# PCBPayloadV8.net
KiCad netlist of a schematic drawn in EAGLE
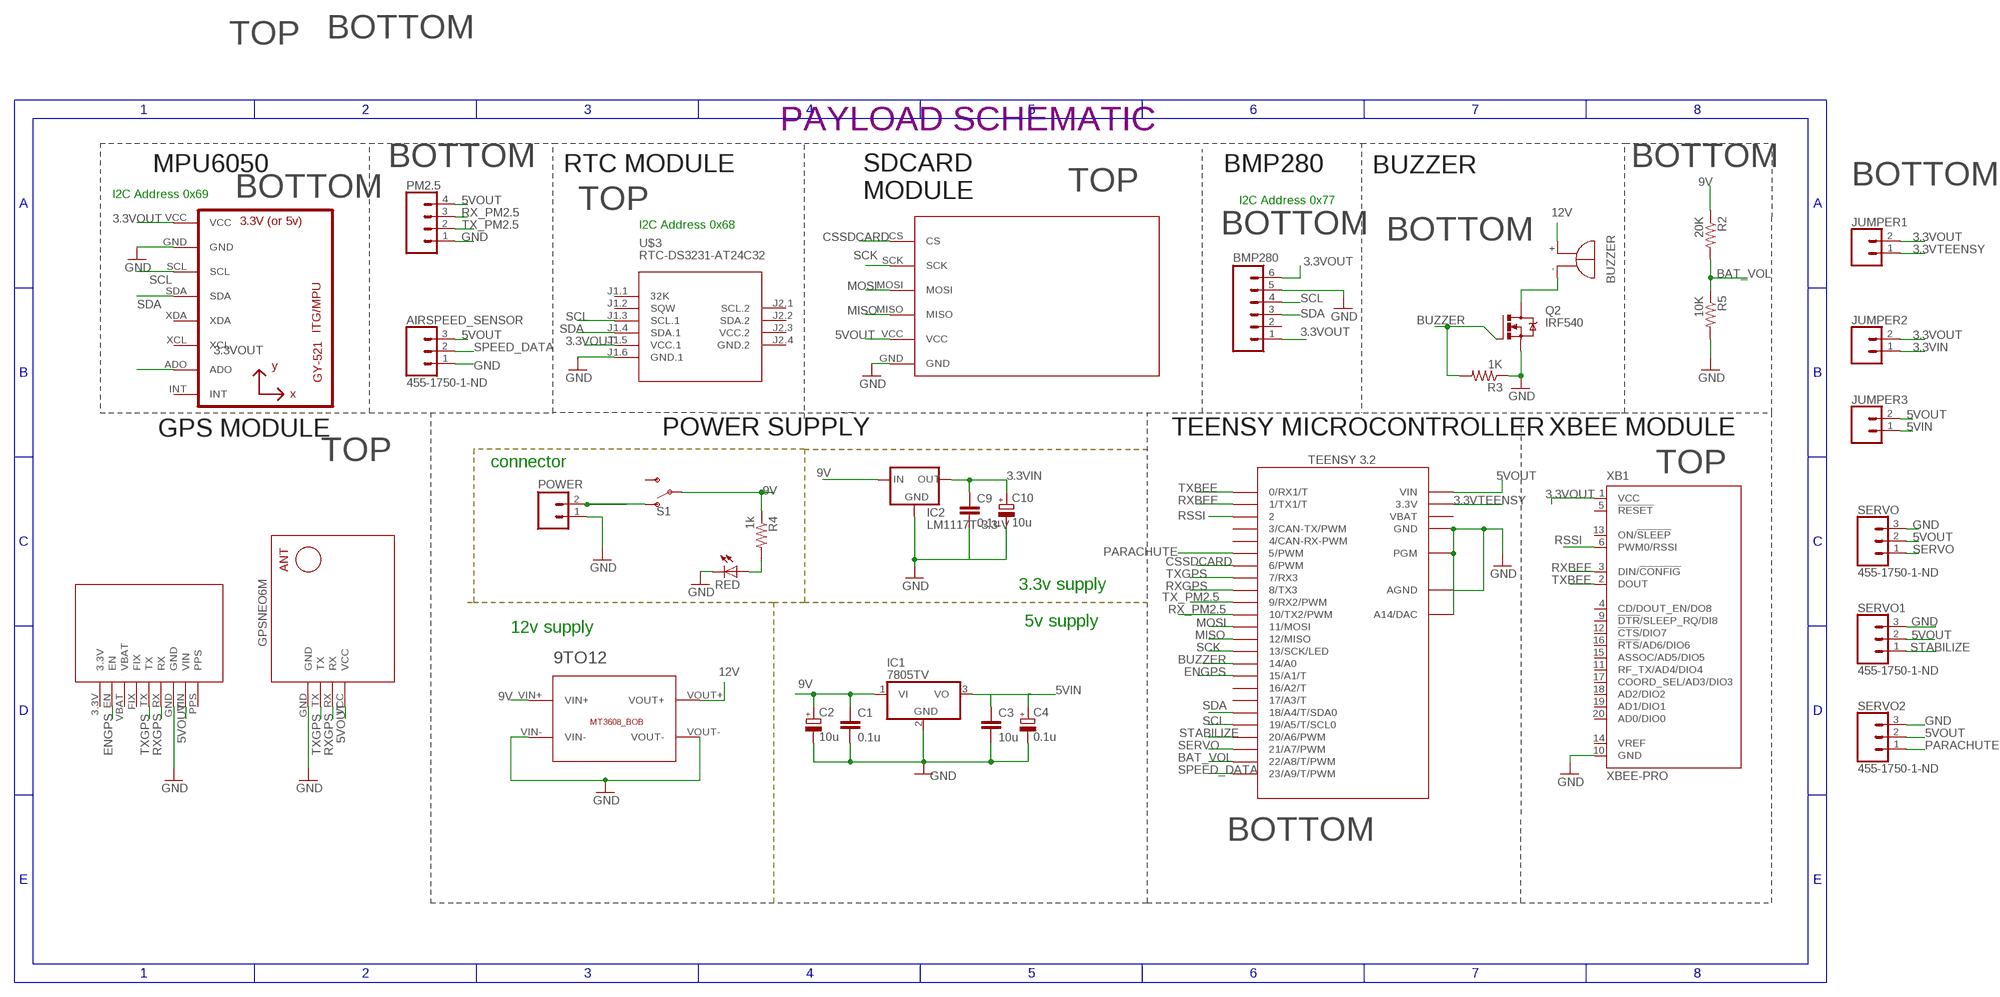
[diagram p0: schematic, sheet 1]

(export (version "E")
  (design (tool "Eeschema 10.0.6"))
  (components
    (comp (ref "9TO12")
      (value "BREAKOUTS_MT3608_BOB")
      (footprint "eagle-import:BREAKOUTS_MT3608_BOB")
      (libsource (lib "eagle-import") (part "BREAKOUTS_MT3608_BOB"))
    )
    (comp (ref "AIRSPEED_SENSOR")
      (value "455-1750-1-ND")
      (footprint "eagle-import:1X03")
      (libsource (lib "eagle-import") (part "CONN_03"))
    )
    (comp (ref "BMP280")
      (value "M06")
      (footprint "eagle-import:06P")
      (libsource (lib "eagle-import") (part "M06"))
    )
    (comp (ref "C1")
      (value "0.1u")
      (footprint "eagle-import:C025-025X050")
      (libsource (lib "eagle-import") (part "C-EU025-025X050"))
    )
    (comp (ref "C2")
      (value "10u")
      (footprint "eagle-import:E2,5-6")
      (libsource (lib "eagle-import") (part "CPOL-EUE2.5-6"))
    )
    (comp (ref "C3")
      (value "10u")
      (footprint "eagle-import:C025-025X050")
      (libsource (lib "eagle-import") (part "C-EU025-025X050"))
    )
    (comp (ref "C4")
      (value "0.1u")
      (footprint "eagle-import:E2,5-6")
      (libsource (lib "eagle-import") (part "CPOL-EUE2.5-6"))
    )
    (comp (ref "C9")
      (value "0.1u")
      (footprint "eagle-import:C025-025X050")
      (libsource (lib "eagle-import") (part "C-EU025-025X050"))
    )
    (comp (ref "C10")
      (value "10u")
      (footprint "eagle-import:E2,5-6")
      (libsource (lib "eagle-import") (part "CPOL-EUE2.5-6"))
    )
    (comp (ref "IC1")
      (value "7805TV")
      (footprint "eagle-import:TO220V")
      (libsource (lib "eagle-import") (part "78TV05"))
    )
    (comp (ref "IC2")
      (value "LM1117T-3.3-V")
      (footprint "eagle-import:TO220V")
      (libsource (lib "eagle-import") (part "LM1117T--V3.3"))
    )
    (comp (ref "JUMPER1")
      (value "CONN_02")
      (footprint "eagle-import:1X02")
      (libsource (lib "eagle-import") (part "CONN_02"))
    )
    (comp (ref "JUMPER2")
      (value "CONN_02")
      (footprint "eagle-import:1X02")
      (libsource (lib "eagle-import") (part "CONN_02"))
    )
    (comp (ref "JUMPER3")
      (value "CONN_02")
      (footprint "eagle-import:1X02")
      (libsource (lib "eagle-import") (part "CONN_02"))
    )
    (comp (ref "PM2.5")
      (value "CONN_04")
      (footprint "eagle-import:1X04")
      (libsource (lib "eagle-import") (part "CONN_04"))
    )
    (comp (ref "POWER")
      (value "CEDT_JANUARY_2015_V5_M02")
      (footprint "eagle-import:CEDT_JANUARY_2015_V5_02P")
      (libsource (lib "eagle-import") (part "CEDT_JANUARY_2015_V5_M02"))
    )
    (comp (ref "Q2")
      (value "IRF540")
      (footprint "eagle-import:TO220BV")
      (libsource (lib "eagle-import") (part "IRF540"))
    )
    (comp (ref "R2")
      (value "20K")
      (footprint "eagle-import:0204_7")
      (libsource (lib "eagle-import") (part "R-US_0204/7"))
    )
    (comp (ref "R3")
      (value "1K")
      (footprint "eagle-import:0204_7")
      (libsource (lib "eagle-import") (part "R-US_0204/7"))
    )
    (comp (ref "R4")
      (value "1k")
      (footprint "eagle-import:0204_7")
      (libsource (lib "eagle-import") (part "R-US_0204/7"))
    )
    (comp (ref "R5")
      (value "10K")
      (footprint "eagle-import:0204_7")
      (libsource (lib "eagle-import") (part "R-US_0204/7"))
    )
    (comp (ref "RED")
      (value "red")
      (footprint "eagle-import:LED3MM")
      (libsource (lib "eagle-import") (part "LED3MM"))
    )
    (comp (ref "S1")
      (value "SWITCH-SPDT-PTH-11.6X4.0MM")
      (footprint "eagle-import:SWITCH_SPDT_PTH_11.6X4.0MM")
      (libsource (lib "eagle-import") (part "SWITCH-SPDT-PTH-11.6X4.0MM"))
    )
    (comp (ref "SERVO")
      (value "455-1750-1-ND")
      (footprint "eagle-import:1X03")
      (libsource (lib "eagle-import") (part "CONN_03"))
    )
    (comp (ref "SERVO1")
      (value "455-1750-1-ND")
      (footprint "eagle-import:1X03")
      (libsource (lib "eagle-import") (part "CONN_03"))
    )
    (comp (ref "SERVO2")
      (value "455-1750-1-ND")
      (footprint "eagle-import:1X03")
      (libsource (lib "eagle-import") (part "CONN_03"))
    )
    (comp (ref "SG1")
      (value "BUZZER_EB2209A")
      (footprint "eagle-import:BUZZER_EB2209A")
      (libsource (lib "eagle-import") (part "BUZZER_EB2209A"))
    )
    (comp (ref "U$1")
      (value "GPS-RECEIVER-NEO6M")
      (footprint "eagle-import:GPS-RECEIVER-NEO6M")
      (libsource (lib "eagle-import") (part "GPS-RECEIVER-NEO6M"))
    )
    (comp (ref "U$2")
      (value "TEENSY_3.1-3.2_OUTER_ROW")
      (footprint "eagle-import:TEENSY_3.0-3.2&LC_OUTER_ROW")
      (libsource (lib "eagle-import") (part "TEENSY_3.1-3.2_OUTER_ROW"))
    )
    (comp (ref "U$3")
      (value "RTC-DS3231-AT24C32")
      (footprint "eagle-import:RTC-DS3231-AT24C32")
      (libsource (lib "eagle-import") (part "RTC-DS3231-AT24C32"))
    )
    (comp (ref "U$4")
      (value "ADAFRUIT_GPS")
      (footprint "eagle-import:ADAFRUIT_GPS")
      (libsource (lib "eagle-import") (part "ADAFRUIT_GPS"))
    )
    (comp (ref "U$5")
      (value "SDCARD")
      (footprint "eagle-import:M0SDCARDMODULE")
      (libsource (lib "eagle-import") (part "SDCARD"))
    )
    (comp (ref "U1")
      (value "GY-521MPU6050")
      (footprint "eagle-import:GY-521")
      (libsource (lib "eagle-import") (part "GY-521MPU6050"))
    )
    (comp (ref "XB1")
      (value "XBEE-PRO")
      (footprint "eagle-import:XBEE-PRO")
      (fields (field (name "MPN") "XBP24-AWI-001"))
      (libsource (lib "eagle-import") (part "XBEE-PRO"))
    )
  )
  (nets
    (net (code "1") (name "/3.3VIN") (class "Default")
      (node (ref "C10") (pin "+") (pinfunction "+_+") (pintype "passive"))
      (node (ref "C9") (pin "1") (pinfunction "1_1") (pintype "passive"))
      (node (ref "IC2") (pin "2") (pinfunction "OUT_2") (pintype "passive"))
      (node (ref "JUMPER2") (pin "1") (pinfunction "1_1") (pintype "passive"))
    )
    (net (code "2") (name "/3.3VOUT") (class "Default")
      (node (ref "BMP280") (pin "1") (pinfunction "1_1") (pintype "passive"))
      (node (ref "BMP280") (pin "6") (pinfunction "6_6") (pintype "passive"))
      (node (ref "JUMPER1") (pin "2") (pinfunction "2_2") (pintype "passive"))
      (node (ref "JUMPER2") (pin "2") (pinfunction "2_2") (pintype "passive"))
      (node (ref "U$3") (pin "J1.5") (pinfunction "VCC.1_J1.5") (pintype "power_in"))
      (node (ref "U1") (pin "ADO") (pinfunction "ADO_ADO") (pintype "bidirectional"))
      (node (ref "U1") (pin "VCC") (pinfunction "VCC_VCC") (pintype "bidirectional"))
      (node (ref "XB1") (pin "1") (pinfunction "VCC_1") (pintype "power_in"))
    )
    (net (code "3") (name "/3.3VTEENSY") (class "Default")
      (node (ref "JUMPER1") (pin "1") (pinfunction "1_1") (pintype "passive"))
      (node (ref "U$2") (pin "3.3V") (pinfunction "3.3V_3.3V") (pintype "power_in"))
      (node (ref "U$2") (pin "3.3V1") (pinfunction "3.3V_3.3V1") (pintype "power_in"))
    )
    (net (code "4") (name "/5VIN") (class "Default")
      (node (ref "C3") (pin "1") (pinfunction "1_1") (pintype "passive"))
      (node (ref "C4") (pin "+") (pinfunction "+_+") (pintype "passive"))
      (node (ref "IC1") (pin "3") (pinfunction "VO_3") (pintype "passive"))
      (node (ref "JUMPER3") (pin "1") (pinfunction "1_1") (pintype "passive"))
    )
    (net (code "5") (name "/5VOUT") (class "Default")
      (node (ref "AIRSPEED_SENSOR") (pin "3") (pinfunction "3_3") (pintype "passive"))
      (node (ref "JUMPER3") (pin "2") (pinfunction "2_2") (pintype "passive"))
      (node (ref "PM2.5") (pin "4") (pinfunction "4_4") (pintype "passive"))
      (node (ref "SERVO") (pin "2") (pinfunction "2_2") (pintype "passive"))
      (node (ref "SERVO1") (pin "2") (pinfunction "2_2") (pintype "passive"))
      (node (ref "SERVO2") (pin "2") (pinfunction "2_2") (pintype "passive"))
      (node (ref "U$1") (pin "VCC") (pinfunction "VCC_VCC") (pintype "power_in"))
      (node (ref "U$2") (pin "VIN") (pinfunction "VIN_VIN") (pintype "power_in"))
      (node (ref "U$4") (pin "VIN") (pinfunction "VIN_VIN") (pintype "bidirectional"))
      (node (ref "U$5") (pin "VCC") (pinfunction "VCC_VCC") (pintype "bidirectional"))
    )
    (net (code "6") (name "/9V") (class "Default")
      (node (ref "9TO12") (pin "VIN+") (pinfunction "VIN+_VIN+") (pintype "bidirectional"))
      (node (ref "C1") (pin "1") (pinfunction "1_1") (pintype "passive"))
      (node (ref "C2") (pin "+") (pinfunction "+_+") (pintype "passive"))
      (node (ref "IC1") (pin "1") (pinfunction "VI_1") (pintype "input"))
      (node (ref "IC2") (pin "3") (pinfunction "IN_3") (pintype "input"))
      (node (ref "R2") (pin "1") (pinfunction "1_1") (pintype "passive"))
      (node (ref "R4") (pin "1") (pinfunction "1_1") (pintype "passive"))
      (node (ref "S1") (pin "2") (pinfunction "P_2") (pintype "passive"))
    )
    (net (code "7") (name "/12V") (class "Default")
      (node (ref "9TO12") (pin "VOUT+") (pinfunction "VOUT+_VOUT+") (pintype "bidirectional"))
      (node (ref "SG1") (pin "+") (pinfunction "+_+") (pintype "passive"))
    )
    (net (code "8") (name "/BAT_VOL") (class "Default")
      (node (ref "R2") (pin "2") (pinfunction "2_2") (pintype "passive"))
      (node (ref "R5") (pin "1") (pinfunction "1_1") (pintype "passive"))
      (node (ref "U$2") (pin "22/A8") (pinfunction "22/A8/T/PWM_22/A8") (pintype "bidirectional"))
    )
    (net (code "9") (name "/BUZZER") (class "Default")
      (node (ref "Q2") (pin "G") (pinfunction "G_G") (pintype "passive"))
      (node (ref "R3") (pin "2") (pinfunction "2_2") (pintype "passive"))
      (node (ref "U$2") (pin "14/A0") (pinfunction "14/A0_14/A0") (pintype "bidirectional"))
    )
    (net (code "10") (name "/CSSDCARD") (class "Default")
      (node (ref "U$2") (pin "6") (pinfunction "6/PWM_6") (pintype "bidirectional"))
      (node (ref "U$5") (pin "CS") (pinfunction "CS_CS") (pintype "bidirectional"))
    )
    (net (code "11") (name "/ENGPS") (class "Default")
      (node (ref "U$2") (pin "15/A1") (pinfunction "15/A1/T_15/A1") (pintype "bidirectional"))
      (node (ref "U$4") (pin "EN") (pinfunction "EN_EN") (pintype "bidirectional"))
    )
    (net (code "12") (name "/GND.2") (class "Default")
      (node (ref "U$3") (pin "J2.4") (pinfunction "GND.2_J2.4") (pintype "power_in"))
    )
    (net (code "13") (name "/MISO") (class "Default")
      (node (ref "U$2") (pin "12") (pinfunction "12/MISO_12") (pintype "bidirectional"))
      (node (ref "U$5") (pin "MISO") (pinfunction "MISO_MISO") (pintype "bidirectional"))
    )
    (net (code "14") (name "/MOSI") (class "Default")
      (node (ref "U$2") (pin "11") (pinfunction "11/MOSI_11") (pintype "bidirectional"))
      (node (ref "U$5") (pin "MOSI") (pinfunction "MOSI_MOSI") (pintype "bidirectional"))
    )
    (net (code "15") (name "/PARACHUTE") (class "Default")
      (node (ref "SERVO2") (pin "1") (pinfunction "1_1") (pintype "passive"))
      (node (ref "U$2") (pin "5") (pinfunction "5/PWM_5") (pintype "bidirectional"))
    )
    (net (code "16") (name "/RSSI") (class "Default")
      (node (ref "U$2") (pin "2") (pinfunction "2_2") (pintype "bidirectional"))
      (node (ref "XB1") (pin "6") (pinfunction "PWM0/RSSI_6") (pintype "output"))
    )
    (net (code "17") (name "/RXBEE") (class "Default")
      (node (ref "U$2") (pin "1") (pinfunction "1/TX1/T_1") (pintype "bidirectional"))
      (node (ref "XB1") (pin "3") (pinfunction "DIN/~{CONFIG}_3") (pintype "input"))
    )
    (net (code "18") (name "/RXGPS") (class "Default")
      (node (ref "U$1") (pin "RX") (pinfunction "RX_RX") (pintype "bidirectional"))
      (node (ref "U$2") (pin "8") (pinfunction "8/TX3_8") (pintype "bidirectional"))
      (node (ref "U$4") (pin "RX") (pinfunction "RX_RX") (pintype "bidirectional"))
    )
    (net (code "19") (name "/RX_PM2.5") (class "Default")
      (node (ref "PM2.5") (pin "3") (pinfunction "3_3") (pintype "passive"))
      (node (ref "U$2") (pin "10") (pinfunction "10/TX2/PWM_10") (pintype "bidirectional"))
    )
    (net (code "20") (name "/SCK") (class "Default")
      (node (ref "U$2") (pin "13") (pinfunction "13/SCK/LED_13") (pintype "bidirectional"))
      (node (ref "U$5") (pin "SCK") (pinfunction "SCK_SCK") (pintype "bidirectional"))
    )
    (net (code "21") (name "/SCL") (class "Default")
      (node (ref "BMP280") (pin "4") (pinfunction "4_4") (pintype "passive"))
      (node (ref "U$2") (pin "19/A5") (pinfunction "19/A5/T/SCL0_19/A5") (pintype "bidirectional"))
      (node (ref "U$3") (pin "J1.3") (pinfunction "SCL.1_J1.3") (pintype "bidirectional"))
      (node (ref "U1") (pin "SCL") (pinfunction "SCL_SCL") (pintype "bidirectional"))
    )
    (net (code "22") (name "/SDA") (class "Default")
      (node (ref "BMP280") (pin "3") (pinfunction "3_3") (pintype "passive"))
      (node (ref "U$2") (pin "18/A4") (pinfunction "18/A4/T/SDA0_18/A4") (pintype "bidirectional"))
      (node (ref "U$3") (pin "J1.4") (pinfunction "SDA.1_J1.4") (pintype "bidirectional"))
      (node (ref "U1") (pin "SDA") (pinfunction "SDA_SDA") (pintype "bidirectional"))
    )
    (net (code "23") (name "/SERVO") (class "Default")
      (node (ref "SERVO") (pin "1") (pinfunction "1_1") (pintype "passive"))
      (node (ref "U$2") (pin "21/A7") (pinfunction "21/A7/PWM_21/A7") (pintype "bidirectional"))
    )
    (net (code "24") (name "/SPEED_DATA") (class "Default")
      (node (ref "AIRSPEED_SENSOR") (pin "2") (pinfunction "2_2") (pintype "passive"))
      (node (ref "U$2") (pin "23/A9") (pinfunction "23/A9/T/PWM_23/A9") (pintype "bidirectional"))
    )
    (net (code "25") (name "/STABILIZE") (class "Default")
      (node (ref "SERVO1") (pin "1") (pinfunction "1_1") (pintype "passive"))
      (node (ref "U$2") (pin "20/A6") (pinfunction "20/A6/PWM_20/A6") (pintype "bidirectional"))
    )
    (net (code "26") (name "/TXBEE") (class "Default")
      (node (ref "U$2") (pin "0") (pinfunction "0/RX1/T_0") (pintype "bidirectional"))
      (node (ref "XB1") (pin "2") (pinfunction "DOUT_2") (pintype "output"))
    )
    (net (code "27") (name "/TXGPS") (class "Default")
      (node (ref "U$1") (pin "TX") (pinfunction "TX_TX") (pintype "bidirectional"))
      (node (ref "U$2") (pin "7") (pinfunction "7/RX3_7") (pintype "bidirectional"))
      (node (ref "U$4") (pin "TX") (pinfunction "TX_TX") (pintype "bidirectional"))
    )
    (net (code "28") (name "/TX_PM2.5") (class "Default")
      (node (ref "PM2.5") (pin "2") (pinfunction "2_2") (pintype "passive"))
      (node (ref "U$2") (pin "9") (pinfunction "9/RX2/PWM_9") (pintype "bidirectional"))
    )
    (net (code "29") (name "/VBAT") (class "Default")
      (node (ref "U$2") (pin "VBAT") (pinfunction "VBAT_VBAT") (pintype "power_in"))
    )
    (net (code "30") (name "/VCC.2") (class "Default")
      (node (ref "U$3") (pin "J2.3") (pinfunction "VCC.2_J2.3") (pintype "power_in"))
    )
    (net (code "31") (name "GND") (class "Default")
      (node (ref "9TO12") (pin "VIN-") (pinfunction "VIN-_VIN-") (pintype "bidirectional"))
      (node (ref "9TO12") (pin "VOUT-") (pinfunction "VOUT-_VOUT-") (pintype "bidirectional"))
      (node (ref "AIRSPEED_SENSOR") (pin "1") (pinfunction "1_1") (pintype "passive"))
      (node (ref "BMP280") (pin "5") (pinfunction "5_5") (pintype "passive"))
      (node (ref "C1") (pin "2") (pinfunction "2_2") (pintype "passive"))
      (node (ref "C10") (pin "-") (pinfunction "-_-") (pintype "passive"))
      (node (ref "C2") (pin "-") (pinfunction "-_-") (pintype "passive"))
      (node (ref "C3") (pin "2") (pinfunction "2_2") (pintype "passive"))
      (node (ref "C4") (pin "-") (pinfunction "-_-") (pintype "passive"))
      (node (ref "C9") (pin "2") (pinfunction "2_2") (pintype "passive"))
      (node (ref "IC1") (pin "2") (pinfunction "GND_2") (pintype "passive"))
      (node (ref "IC2") (pin "1") (pinfunction "GND_1") (pintype "input"))
      (node (ref "PM2.5") (pin "1") (pinfunction "1_1") (pintype "passive"))
      (node (ref "POWER") (pin "1") (pinfunction "1_1") (pintype "passive"))
      (node (ref "Q2") (pin "S") (pinfunction "S_S") (pintype "passive"))
      (node (ref "R3") (pin "1") (pinfunction "1_1") (pintype "passive"))
      (node (ref "R5") (pin "2") (pinfunction "2_2") (pintype "passive"))
      (node (ref "RED") (pin "K") (pinfunction "C_K") (pintype "passive"))
      (node (ref "SERVO") (pin "3") (pinfunction "3_3") (pintype "passive"))
      (node (ref "SERVO1") (pin "3") (pinfunction "3_3") (pintype "passive"))
      (node (ref "SERVO2") (pin "3") (pinfunction "3_3") (pintype "passive"))
      (node (ref "U$1") (pin "GND") (pinfunction "GND_GND") (pintype "bidirectional"))
      (node (ref "U$2") (pin "AGND") (pinfunction "AGND_AGND") (pintype "power_in"))
      (node (ref "U$2") (pin "GND") (pinfunction "GND_GND") (pintype "power_in"))
      (node (ref "U$2") (pin "GND1") (pinfunction "GND_GND1") (pintype "power_in"))
      (node (ref "U$2") (pin "PGM") (pinfunction "PGM_PGM") (pintype "bidirectional"))
      (node (ref "U$2") (pin "RESET/DAC") (pinfunction "A14/DAC_RESET/DAC") (pintype "bidirectional"))
      (node (ref "U$3") (pin "J1.6") (pinfunction "GND.1_J1.6") (pintype "power_in"))
      (node (ref "U$4") (pin "GND") (pinfunction "GND_GND") (pintype "bidirectional"))
      (node (ref "U$5") (pin "GND") (pinfunction "GND_GND") (pintype "bidirectional"))
      (node (ref "U1") (pin "GND") (pinfunction "GND_GND") (pintype "bidirectional"))
      (node (ref "XB1") (pin "10") (pinfunction "GND_10") (pintype "power_in"))
    )
    (net (code "32") (name "Net-(Q2-PadD)") (class "Default")
      (node (ref "Q2") (pin "D") (pinfunction "D_D") (pintype "passive"))
      (node (ref "SG1") (pin "-") (pinfunction "-_-") (pintype "passive"))
    )
    (net (code "33") (name "Net-(R4-Pad2)") (class "Default")
      (node (ref "R4") (pin "2") (pinfunction "2_2") (pintype "passive"))
      (node (ref "RED") (pin "A") (pinfunction "A_A") (pintype "passive"))
    )
    (net (code "34") (name "Net-(S1-O)") (class "Default")
      (node (ref "POWER") (pin "2") (pinfunction "2_2") (pintype "passive"))
      (node (ref "S1") (pin "1") (pinfunction "O_1") (pintype "passive"))
    )
    (net (code "35") (name "unconnected-(BMP280-Pad2)") (class "Default")
      (node (ref "BMP280") (pin "2") (pinfunction "2_2") (pintype "passive"))
    )
    (net (code "36") (name "unconnected-(S1-S-Pad3)") (class "Default")
      (node (ref "S1") (pin "3") (pinfunction "S_3") (pintype "passive"))
    )
    (net (code "37") (name "unconnected-(U$2-3{slash}CAN-TX{slash}PWM-Pad3)") (class "Default")
      (node (ref "U$2") (pin "3") (pinfunction "3/CAN-TX/PWM_3") (pintype "bidirectional"))
    )
    (net (code "38") (name "unconnected-(U$2-4{slash}CAN-RX-PWM-Pad4)") (class "Default")
      (node (ref "U$2") (pin "4") (pinfunction "4/CAN-RX-PWM_4") (pintype "bidirectional"))
    )
    (net (code "39") (name "unconnected-(U$2-16{slash}A2{slash}T-Pad16{slash}A2)") (class "Default")
      (node (ref "U$2") (pin "16/A2") (pinfunction "16/A2/T_16/A2") (pintype "bidirectional"))
    )
    (net (code "40") (name "unconnected-(U$2-17{slash}A3{slash}T-Pad17{slash}A3)") (class "Default")
      (node (ref "U$2") (pin "17/A3") (pinfunction "17/A3/T_17/A3") (pintype "bidirectional"))
    )
    (net (code "41") (name "unconnected-(U$3-32K-PadJ1.1)") (class "Default")
      (node (ref "U$3") (pin "J1.1") (pinfunction "32K_J1.1") (pintype "bidirectional"))
    )
    (net (code "42") (name "unconnected-(U$3-SCL.2-PadJ2.1)") (class "Default")
      (node (ref "U$3") (pin "J2.1") (pinfunction "SCL.2_J2.1") (pintype "bidirectional"))
    )
    (net (code "43") (name "unconnected-(U$3-SDA.2-PadJ2.2)") (class "Default")
      (node (ref "U$3") (pin "J2.2") (pinfunction "SDA.2_J2.2") (pintype "bidirectional"))
    )
    (net (code "44") (name "unconnected-(U$3-SQW-PadJ1.2)") (class "Default")
      (node (ref "U$3") (pin "J1.2") (pinfunction "SQW_J1.2") (pintype "bidirectional"))
    )
    (net (code "45") (name "unconnected-(U$4-Pad3.3V)") (class "Default")
      (node (ref "U$4") (pin "3.3V") (pinfunction "3.3V_3.3V") (pintype "bidirectional"))
    )
    (net (code "46") (name "unconnected-(U$4-PadFIX)") (class "Default")
      (node (ref "U$4") (pin "FIX") (pinfunction "FIX_FIX") (pintype "bidirectional"))
    )
    (net (code "47") (name "unconnected-(U$4-PadPPS)") (class "Default")
      (node (ref "U$4") (pin "PPS") (pinfunction "PPS_PPS") (pintype "bidirectional"))
    )
    (net (code "48") (name "unconnected-(U$4-PadVBAT)") (class "Default")
      (node (ref "U$4") (pin "VBAT") (pinfunction "VBAT_VBAT") (pintype "bidirectional"))
    )
    (net (code "49") (name "unconnected-(U1-PadINT)") (class "Default")
      (node (ref "U1") (pin "INT") (pinfunction "INT_INT") (pintype "bidirectional"))
    )
    (net (code "50") (name "unconnected-(U1-PadXCL)") (class "Default")
      (node (ref "U1") (pin "XCL") (pinfunction "XCL_XCL") (pintype "bidirectional"))
    )
    (net (code "51") (name "unconnected-(U1-PadXDA)") (class "Default")
      (node (ref "U1") (pin "XDA") (pinfunction "XDA_XDA") (pintype "bidirectional"))
    )
    (net (code "52") (name "unconnected-(XB1-AD0{slash}DIO0-Pad20)") (class "Default")
      (node (ref "XB1") (pin "20") (pinfunction "AD0/DIO0_20") (pintype "bidirectional"))
    )
    (net (code "53") (name "unconnected-(XB1-AD1{slash}DIO1-Pad19)") (class "Default")
      (node (ref "XB1") (pin "19") (pinfunction "AD1/DIO1_19") (pintype "bidirectional"))
    )
    (net (code "54") (name "unconnected-(XB1-AD2{slash}DIO2-Pad18)") (class "Default")
      (node (ref "XB1") (pin "18") (pinfunction "AD2/DIO2_18") (pintype "bidirectional"))
    )
    (net (code "55") (name "unconnected-(XB1-ASSOC{slash}AD5{slash}DIO5-Pad15)") (class "Default")
      (node (ref "XB1") (pin "15") (pinfunction "ASSOC/AD5/DIO5_15") (pintype "bidirectional"))
    )
    (net (code "56") (name "unconnected-(XB1-CD{slash}DOUT_EN{slash}DO8-Pad4)") (class "Default")
      (node (ref "XB1") (pin "4") (pinfunction "CD/DOUT_EN/DO8_4") (pintype "output"))
    )
    (net (code "57") (name "unconnected-(XB1-COORD_SEL{slash}AD3{slash}DIO3-Pad17)") (class "Default")
      (node (ref "XB1") (pin "17") (pinfunction "COORD_SEL/AD3/DIO3_17") (pintype "bidirectional"))
    )
    (net (code "58") (name "unconnected-(XB1-ON{slash}~{SLEEP}-Pad13)") (class "Default")
      (node (ref "XB1") (pin "13") (pinfunction "ON/~{SLEEP}_13") (pintype "output"))
    )
    (net (code "59") (name "unconnected-(XB1-RF_TX{slash}AD4{slash}DIO4-Pad11)") (class "Default")
      (node (ref "XB1") (pin "11") (pinfunction "RF_TX/AD4/DIO4_11") (pintype "bidirectional"))
    )
    (net (code "60") (name "unconnected-(XB1-VREF-Pad14)") (class "Default")
      (node (ref "XB1") (pin "14") (pinfunction "VREF_14") (pintype "input"))
    )
    (net (code "61") (name "unconnected-(XB1-~{CTS}{slash}DIO7-Pad12)") (class "Default")
      (node (ref "XB1") (pin "12") (pinfunction "~{CTS}/DIO7_12") (pintype "bidirectional"))
    )
    (net (code "62") (name "unconnected-(XB1-~{DTR}{slash}SLEEP_RQ{slash}DI8-Pad9)") (class "Default")
      (node (ref "XB1") (pin "9") (pinfunction "~{DTR}/SLEEP_RQ/DI8_9") (pintype "bidirectional"))
    )
    (net (code "63") (name "unconnected-(XB1-~{RESET}-Pad5)") (class "Default")
      (node (ref "XB1") (pin "5") (pinfunction "~{RESET}_5") (pintype "input"))
    )
    (net (code "64") (name "unconnected-(XB1-~{RTS}{slash}AD6{slash}DIO6-Pad16)") (class "Default")
      (node (ref "XB1") (pin "16") (pinfunction "~{RTS}/AD6/DIO6_16") (pintype "bidirectional"))
    )
  )
)
